# IceCream_interface_board.net
KiCad netlist of a schematic drawn in EAGLE
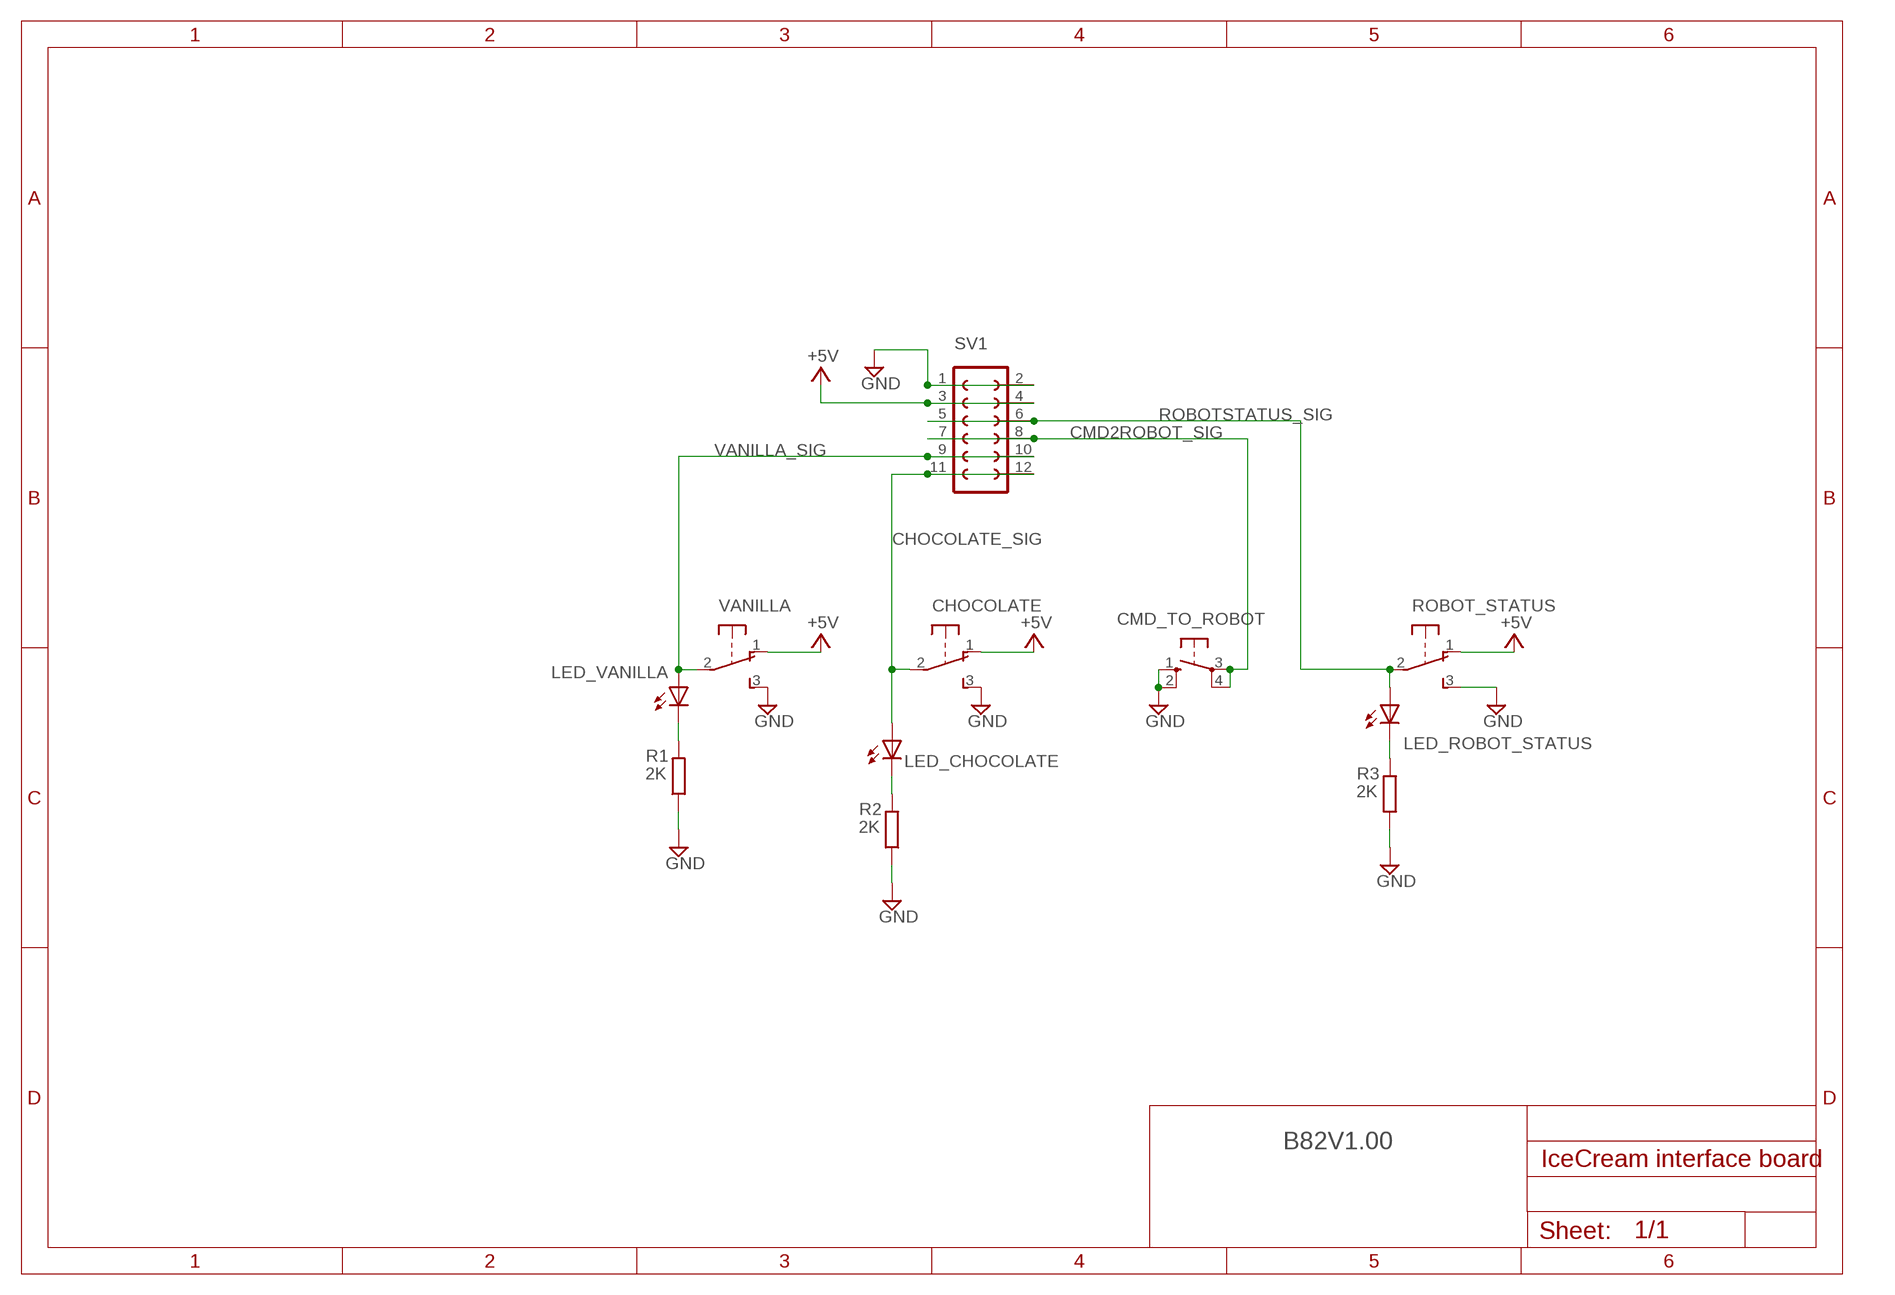
[diagram p0: schematic, sheet 1]

(export (version "E")
  (design (tool "Eeschema 10.0.6"))
  (components
    (comp (ref "CHOCOLATE")
      (value "TOGGLE_SW")
      (footprint "eagle-import:MA03-1")
      (libsource (lib "eagle-import") (part "TOGGLE_SW"))
    )
    (comp (ref "CMD_TO_ROBOT")
      (value "TACT_SWITCH")
      (footprint "eagle-import:B3F-10XX")
      (libsource (lib "eagle-import") (part "TACT_SWITCH"))
    )
    (comp (ref "LED_CHOCOLATE")
      (value "LED5MM")
      (footprint "eagle-import:LED5MM")
      (libsource (lib "eagle-import") (part "LED5MM"))
    )
    (comp (ref "LED_ROBOT_STATUS")
      (value "LED5MM")
      (footprint "eagle-import:LED5MM")
      (libsource (lib "eagle-import") (part "LED5MM"))
    )
    (comp (ref "LED_VANILLA")
      (value "LED5MM")
      (footprint "eagle-import:LED5MM")
      (libsource (lib "eagle-import") (part "LED5MM"))
    )
    (comp (ref "R1")
      (value "2K")
      (footprint "eagle-import:0207_10")
      (libsource (lib "eagle-import") (part "R-EU_0207/10"))
    )
    (comp (ref "R2")
      (value "2K")
      (footprint "eagle-import:0207_10")
      (libsource (lib "eagle-import") (part "R-EU_0207/10"))
    )
    (comp (ref "R3")
      (value "2K")
      (footprint "eagle-import:0207_10")
      (libsource (lib "eagle-import") (part "R-EU_0207/10"))
    )
    (comp (ref "ROBOT_STATUS")
      (value "TOGGLE_SW")
      (footprint "eagle-import:MA03-1")
      (libsource (lib "eagle-import") (part "TOGGLE_SW"))
    )
    (comp (ref "SV1")
      (value "FE06-2")
      (footprint "eagle-import:FE06-2")
      (libsource (lib "eagle-import") (part "FE06-2"))
    )
    (comp (ref "VANILLA")
      (value "TOGGLE_SW")
      (footprint "eagle-import:MA03-1")
      (libsource (lib "eagle-import") (part "TOGGLE_SW"))
    )
  )
  (nets
    (net (code "1") (name "+5V") (class "Default")
      (node (ref "CHOCOLATE") (pin "1") (pinfunction "O_1") (pintype "passive"))
      (node (ref "ROBOT_STATUS") (pin "1") (pinfunction "O_1") (pintype "passive"))
      (node (ref "SV1") (pin "3") (pinfunction "3_3") (pintype "passive"))
      (node (ref "SV1") (pin "4") (pinfunction "4_4") (pintype "passive"))
      (node (ref "VANILLA") (pin "1") (pinfunction "O_1") (pintype "passive"))
    )
    (net (code "2") (name "/CHOCOLATE_SIG") (class "Default")
      (node (ref "CHOCOLATE") (pin "2") (pinfunction "P_2") (pintype "passive"))
      (node (ref "LED_CHOCOLATE") (pin "A") (pinfunction "A_A") (pintype "passive"))
      (node (ref "SV1") (pin "11") (pinfunction "11_11") (pintype "passive"))
      (node (ref "SV1") (pin "12") (pinfunction "12_12") (pintype "passive"))
    )
    (net (code "3") (name "/CMD2ROBOT_SIG") (class "Default")
      (node (ref "CMD_TO_ROBOT") (pin "3") (pinfunction "P_3") (pintype "passive"))
      (node (ref "CMD_TO_ROBOT") (pin "4") (pinfunction "P1_4") (pintype "passive"))
      (node (ref "SV1") (pin "7") (pinfunction "7_7") (pintype "passive"))
      (node (ref "SV1") (pin "8") (pinfunction "8_8") (pintype "passive"))
    )
    (net (code "4") (name "/ROBOTSTATUS_SIG") (class "Default")
      (node (ref "LED_ROBOT_STATUS") (pin "A") (pinfunction "A_A") (pintype "passive"))
      (node (ref "ROBOT_STATUS") (pin "2") (pinfunction "P_2") (pintype "passive"))
      (node (ref "SV1") (pin "5") (pinfunction "5_5") (pintype "passive"))
      (node (ref "SV1") (pin "6") (pinfunction "6_6") (pintype "passive"))
    )
    (net (code "5") (name "/VANILLA_SIG") (class "Default")
      (node (ref "LED_VANILLA") (pin "A") (pinfunction "A_A") (pintype "passive"))
      (node (ref "SV1") (pin "10") (pinfunction "10_10") (pintype "passive"))
      (node (ref "SV1") (pin "9") (pinfunction "9_9") (pintype "passive"))
      (node (ref "VANILLA") (pin "2") (pinfunction "P_2") (pintype "passive"))
    )
    (net (code "6") (name "GND") (class "Default")
      (node (ref "CHOCOLATE") (pin "3") (pinfunction "S_3") (pintype "passive"))
      (node (ref "CMD_TO_ROBOT") (pin "1") (pinfunction "S_1") (pintype "passive"))
      (node (ref "CMD_TO_ROBOT") (pin "2") (pinfunction "S1_2") (pintype "passive"))
      (node (ref "R1") (pin "1") (pinfunction "1_1") (pintype "passive"))
      (node (ref "R2") (pin "1") (pinfunction "1_1") (pintype "passive"))
      (node (ref "R3") (pin "1") (pinfunction "1_1") (pintype "passive"))
      (node (ref "ROBOT_STATUS") (pin "3") (pinfunction "S_3") (pintype "passive"))
      (node (ref "SV1") (pin "1") (pinfunction "1_1") (pintype "passive"))
      (node (ref "SV1") (pin "2") (pinfunction "2_2") (pintype "passive"))
      (node (ref "VANILLA") (pin "3") (pinfunction "S_3") (pintype "passive"))
    )
    (net (code "7") (name "Net-(LED_CHOCOLATE-C)") (class "Default")
      (node (ref "LED_CHOCOLATE") (pin "K") (pinfunction "C_K") (pintype "passive"))
      (node (ref "R2") (pin "2") (pinfunction "2_2") (pintype "passive"))
    )
    (net (code "8") (name "Net-(LED_ROBOT_STATUS-C)") (class "Default")
      (node (ref "LED_ROBOT_STATUS") (pin "K") (pinfunction "C_K") (pintype "passive"))
      (node (ref "R3") (pin "2") (pinfunction "2_2") (pintype "passive"))
    )
    (net (code "9") (name "Net-(LED_VANILLA-C)") (class "Default")
      (node (ref "LED_VANILLA") (pin "K") (pinfunction "C_K") (pintype "passive"))
      (node (ref "R1") (pin "2") (pinfunction "2_2") (pintype "passive"))
    )
  )
)
